# 5V_REG.net
KiCad netlist of a schematic drawn in Altium Designer
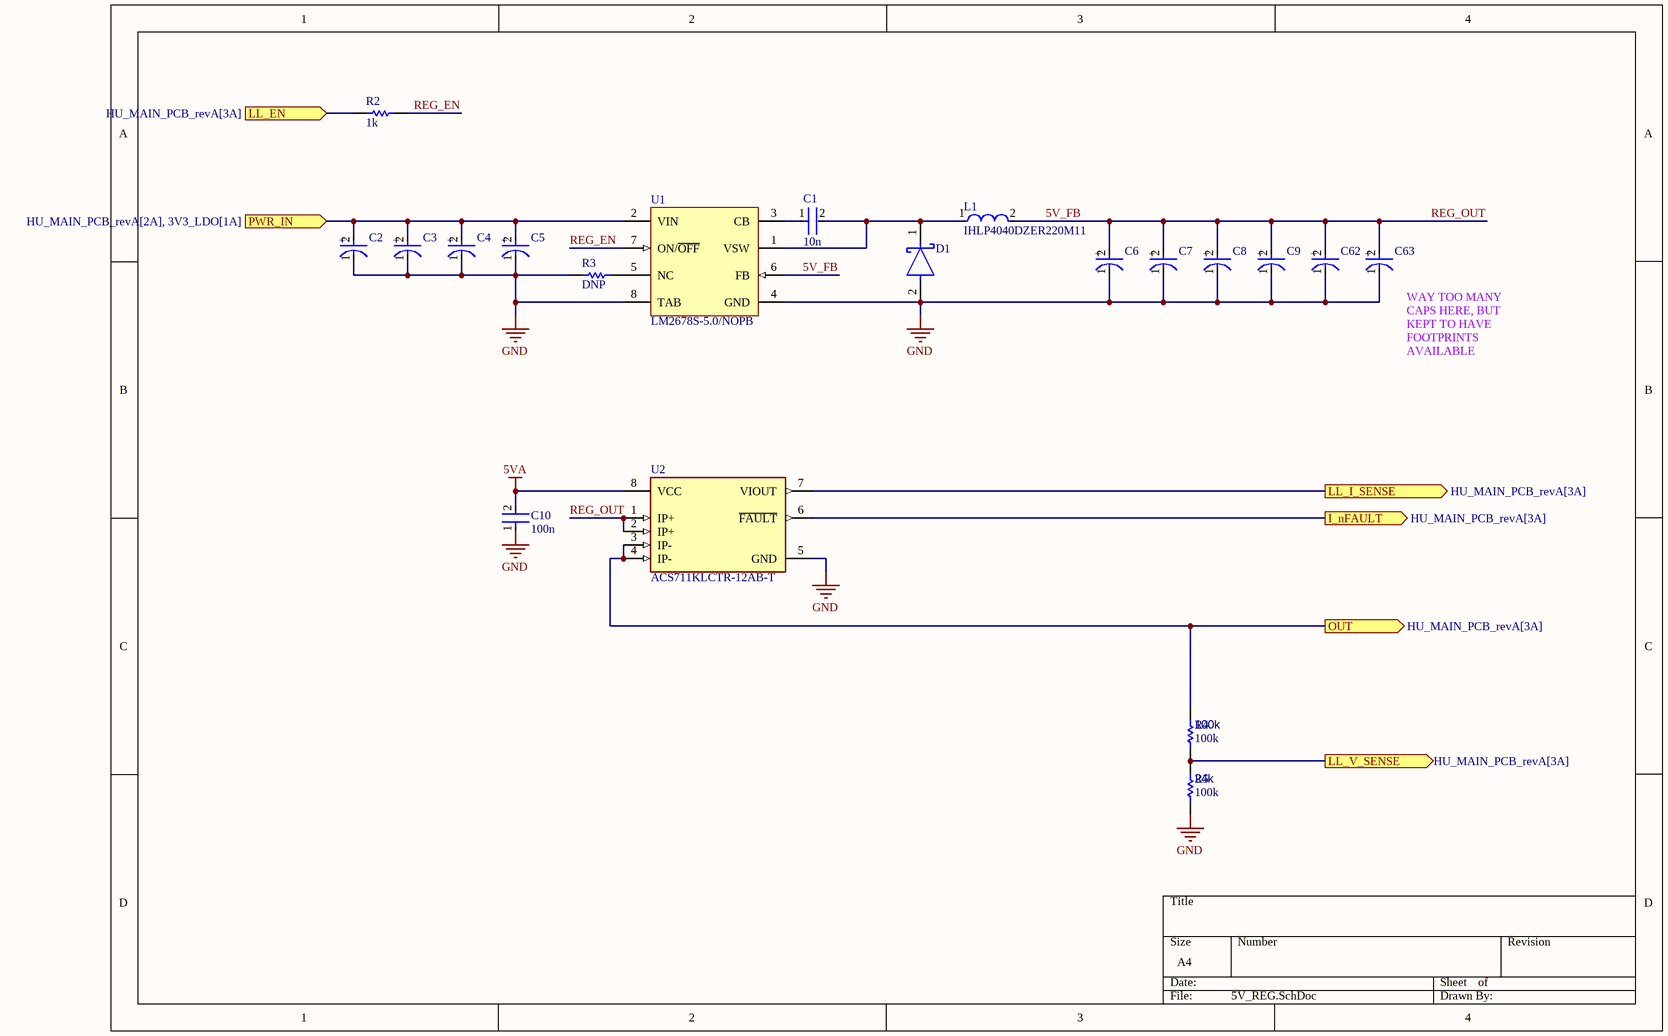
[diagram p0: 5V_REG.SchDoc]

(export (version "E")
  (design (tool "Eeschema 10.0.6"))
  (components
    (comp (ref "C1")
      (value "10n")
      (footprint "FP-0402-L_1_0_0_05-W_0_5-IPC_A")
      (description "LARGE PADS, 0402 CAP, CHANGE COMMENT TO MATCH REAL P/N")
      (libsource (lib "Space Concordia") (part "b4654b650e69147ec39a6b967a45e02"))
    )
    (comp (ref "C2")
      (value "TPSE686K025R0125")
      (footprint "FP-TPSE-MFG")
      (description "CAP TANT 68UF 10% 25V 2917")
      (fields (field (name "VOLTAGE") "25V") (field (name "TOLERANCE") "10%"))
      (libsource (lib "Altium Content Vault") (part "203bc49f2ac43e59fd269a8c329ed05"))
    )
    (comp (ref "C3")
      (value "TPSE686K025R0125")
      (footprint "FP-TPSE-MFG")
      (description "CAP TANT 68UF 10% 25V 2917")
      (fields (field (name "VOLTAGE") "25V") (field (name "TOLERANCE") "10%"))
      (libsource (lib "Altium Content Vault") (part "203bc49f2ac43e59fd269a8c329ed05"))
    )
    (comp (ref "C4")
      (value "TPSE686K025R0125")
      (footprint "FP-TPSE-MFG")
      (description "CAP TANT 68UF 10% 25V 2917")
      (fields (field (name "VOLTAGE") "25V") (field (name "TOLERANCE") "10%"))
      (libsource (lib "Altium Content Vault") (part "203bc49f2ac43e59fd269a8c329ed05"))
    )
    (comp (ref "C5")
      (value "TPSE686K025R0125")
      (footprint "FP-TPSE-MFG")
      (description "CAP TANT 68UF 10% 25V 2917")
      (fields (field (name "VOLTAGE") "25V") (field (name "TOLERANCE") "10%"))
      (libsource (lib "Altium Content Vault") (part "203bc49f2ac43e59fd269a8c329ed05"))
    )
    (comp (ref "C6")
      (value "TPSE686K025R0125")
      (footprint "FP-TPSE-MFG")
      (description "CAP TANT 68UF 10% 25V 2917")
      (fields (field (name "VOLTAGE") "25V") (field (name "TOLERANCE") "10%"))
      (libsource (lib "Altium Content Vault") (part "203bc49f2ac43e59fd269a8c329ed05"))
    )
    (comp (ref "C7")
      (value "TPSE686K025R0125")
      (footprint "FP-TPSE-MFG")
      (description "CAP TANT 68UF 10% 25V 2917")
      (fields (field (name "VOLTAGE") "25V") (field (name "TOLERANCE") "10%"))
      (libsource (lib "Altium Content Vault") (part "203bc49f2ac43e59fd269a8c329ed05"))
    )
    (comp (ref "C8")
      (value "TPSE686K025R0125")
      (footprint "FP-TPSE-MFG")
      (description "CAP TANT 68UF 10% 25V 2917")
      (fields (field (name "VOLTAGE") "25V") (field (name "TOLERANCE") "10%"))
      (libsource (lib "Altium Content Vault") (part "203bc49f2ac43e59fd269a8c329ed05"))
    )
    (comp (ref "C9")
      (value "TPSE686K025R0125")
      (footprint "FP-TPSE-MFG")
      (description "CAP TANT 68UF 10% 25V 2917")
      (fields (field (name "VOLTAGE") "25V") (field (name "TOLERANCE") "10%"))
      (libsource (lib "Altium Content Vault") (part "203bc49f2ac43e59fd269a8c329ed05"))
    )
    (comp (ref "C10")
      (value "100n")
      (footprint "FP-0402-L_1_0_0_05-W_0_5-IPC_A")
      (description "LARGE PADS, 0402 CAP, CHANGE COMMENT TO MATCH REAL P/N")
      (libsource (lib "Space Concordia") (part "b4654b650e69147ec39a6b967a45e02"))
    )
    (comp (ref "C62")
      (value "TPSE686K025R0125")
      (footprint "FP-TPSE-MFG")
      (description "CAP TANT 68UF 10% 25V 2917")
      (fields (field (name "VOLTAGE") "25V") (field (name "TOLERANCE") "10%"))
      (libsource (lib "Altium Content Vault") (part "203bc49f2ac43e59fd269a8c329ed05"))
    )
    (comp (ref "C63")
      (value "TPSE686K025R0125")
      (footprint "FP-TPSE-MFG")
      (description "CAP TANT 68UF 10% 25V 2917")
      (fields (field (name "VOLTAGE") "25V") (field (name "TOLERANCE") "10%"))
      (libsource (lib "Altium Content Vault") (part "203bc49f2ac43e59fd269a8c329ed05"))
    )
    (comp (ref "D1")
      (value "B540C-13-F")
      (footprint "FP-SMC-MFG")
      (description "DIODE SCHOTTKY 40V 5A SMC")
      (fields
        (field (name "OCTOPART") "https://octopart.com/b540c-13-f-diodes+inc.-325873")
        (field (name "MANUFACTURER") "Diodes Inc.")
      )
      (libsource (lib "Altium Content Vault") (part "1d6ec82d83fb6aee721767c19dac4b9"))
    )
    (comp (ref "L1")
      (value "IHLP4040DZER220M11")
      (footprint "FP-IHLP-4040DZ-FP_3_124x3-MFG")
      (description "Commercial Inductors, Low DCR Series 22uH 5A 66mΩ 20%")
      (fields (field (name "TOLERANCE") "20%"))
      (libsource (lib "Altium Content Vault") (part "725321dda6339637d4d059423bc1c3c"))
    )
    (comp (ref "R2")
      (value "1k")
      (footprint "R0603B")
      (description "Resistor")
      (libsource (lib "Space Concordia") (part "Resistor"))
    )
    (comp (ref "R3")
      (value "DNP")
      (footprint "R0603B")
      (description "Resistor")
      (libsource (lib "Space Concordia") (part "Resistor"))
    )
    (comp (ref "R4")
      (value "100k")
      (footprint "R0603B")
      (description "Resistor")
      (fields (field (name "ALTIUM_VALUE") "100k"))
      (libsource (lib "Space Concordia") (part "Resistor"))
    )
    (comp (ref "R5")
      (value "100k")
      (footprint "R0603B")
      (description "Resistor")
      (fields (field (name "ALTIUM_VALUE") "24k"))
      (libsource (lib "Space Concordia") (part "Resistor"))
    )
    (comp (ref "U1")
      (value "LM2678S-5.0/NOPB")
      (footprint "KTW0007B_L")
      (description "SIMPLE SWITCHER® High Efficiency 5A Step-Down Voltage Regulator, 7-pin TO-263, Pb-Free")
      (fields (field (name "MANUFACTURER") "Texas Instruments"))
      (libsource (lib "Altium Content Vault") (part "PM-REG-LM2678S"))
    )
    (comp (ref "U2")
      (value "ACS711KLCTR-12AB-T")
      (footprint "FP-LC-8-IPC_C")
      (description "SENSOR CURRENT HALL 12.5A AC/DC")
      (libsource (lib "Altium Content Vault") (part "b5e82308d4912bad35d89a98a7a92f9"))
    )
  )
  (nets
    (net (code "1") (name "/5V_FB") (class "Default")
      (node (ref "C6") (pin "2") (pinfunction "A_2") (pintype "passive"))
      (node (ref "C62") (pin "2") (pinfunction "A_2") (pintype "passive"))
      (node (ref "C63") (pin "2") (pinfunction "A_2") (pintype "passive"))
      (node (ref "C7") (pin "2") (pinfunction "A_2") (pintype "passive"))
      (node (ref "C8") (pin "2") (pinfunction "A_2") (pintype "passive"))
      (node (ref "C9") (pin "2") (pinfunction "A_2") (pintype "passive"))
      (node (ref "L1") (pin "2") (pinfunction "2_2") (pintype "passive"))
      (node (ref "U1") (pin "6") (pinfunction "FB_6") (pintype "input"))
      (node (ref "U2") (pin "1") (pinfunction "IP+_1") (pintype "input"))
      (node (ref "U2") (pin "2") (pinfunction "IP+_2") (pintype "input"))
    )
    (net (code "2") (name "/I_nFAULT") (class "Default")
      (node (ref "U2") (pin "6") (pinfunction "~{FAULT}_6") (pintype "output"))
    )
    (net (code "3") (name "/LL_EN") (class "Default")
      (node (ref "R2") (pin "2") (pinfunction "2_2") (pintype "passive"))
    )
    (net (code "4") (name "/LL_I_SENSE") (class "Default")
      (node (ref "U2") (pin "7") (pinfunction "VIOUT_7") (pintype "output"))
    )
    (net (code "5") (name "/LL_V_SENSE") (class "Default")
      (node (ref "R4") (pin "1") (pinfunction "1_1") (pintype "passive"))
      (node (ref "R5") (pin "2") (pinfunction "2_2") (pintype "passive"))
    )
    (net (code "6") (name "/OUT") (class "Default")
      (node (ref "R4") (pin "2") (pinfunction "2_2") (pintype "passive"))
      (node (ref "U2") (pin "3") (pinfunction "IP-_3") (pintype "input"))
      (node (ref "U2") (pin "4") (pinfunction "IP-_4") (pintype "input"))
    )
    (net (code "7") (name "/PWR_IN") (class "Default")
      (node (ref "C2") (pin "2") (pinfunction "A_2") (pintype "passive"))
      (node (ref "C3") (pin "2") (pinfunction "A_2") (pintype "passive"))
      (node (ref "C4") (pin "2") (pinfunction "A_2") (pintype "passive"))
      (node (ref "C5") (pin "2") (pinfunction "A_2") (pintype "passive"))
      (node (ref "U1") (pin "2") (pinfunction "VIN_2") (pintype "power_in"))
    )
    (net (code "8") (name "/REG_EN") (class "Default")
      (node (ref "R2") (pin "1") (pinfunction "1_1") (pintype "passive"))
      (node (ref "U1") (pin "7") (pinfunction "ON/~{OFF}_7") (pintype "input"))
    )
    (net (code "9") (name "5VA") (class "Default")
      (node (ref "C10") (pin "2") (pinfunction "2_2") (pintype "passive"))
      (node (ref "U2") (pin "8") (pinfunction "VCC_8") (pintype "power_in"))
    )
    (net (code "10") (name "GND") (class "Default")
      (node (ref "C10") (pin "1") (pinfunction "1_1") (pintype "passive"))
      (node (ref "C2") (pin "1") (pinfunction "C_1") (pintype "passive"))
      (node (ref "C3") (pin "1") (pinfunction "C_1") (pintype "passive"))
      (node (ref "C4") (pin "1") (pinfunction "C_1") (pintype "passive"))
      (node (ref "C5") (pin "1") (pinfunction "C_1") (pintype "passive"))
      (node (ref "C6") (pin "1") (pinfunction "C_1") (pintype "passive"))
      (node (ref "C62") (pin "1") (pinfunction "C_1") (pintype "passive"))
      (node (ref "C63") (pin "1") (pinfunction "C_1") (pintype "passive"))
      (node (ref "C7") (pin "1") (pinfunction "C_1") (pintype "passive"))
      (node (ref "C8") (pin "1") (pinfunction "C_1") (pintype "passive"))
      (node (ref "C9") (pin "1") (pinfunction "C_1") (pintype "passive"))
      (node (ref "D1") (pin "2") (pinfunction "A_2") (pintype "passive"))
      (node (ref "R3") (pin "2") (pinfunction "2_2") (pintype "passive"))
      (node (ref "R5") (pin "1") (pinfunction "1_1") (pintype "passive"))
      (node (ref "U1") (pin "4") (pinfunction "GND_4") (pintype "power_in"))
      (node (ref "U1") (pin "8") (pinfunction "TAB_8") (pintype "power_in"))
      (node (ref "U2") (pin "5") (pinfunction "GND_5") (pintype "power_in"))
    )
    (net (code "11") (name "Net-(D1-C)") (class "Default")
      (node (ref "C1") (pin "2") (pinfunction "2_2") (pintype "passive"))
      (node (ref "D1") (pin "1") (pinfunction "C_1") (pintype "passive"))
      (node (ref "L1") (pin "1") (pinfunction "1_1") (pintype "passive"))
      (node (ref "U1") (pin "1") (pinfunction "VSW_1") (pintype "power_in"))
    )
    (net (code "12") (name "Net-(U1-CB)") (class "Default")
      (node (ref "C1") (pin "1") (pinfunction "1_1") (pintype "passive"))
      (node (ref "U1") (pin "3") (pinfunction "CB_3") (pintype "passive"))
    )
    (net (code "13") (name "Net-(U1-NC)") (class "Default")
      (node (ref "R3") (pin "1") (pinfunction "1_1") (pintype "passive"))
      (node (ref "U1") (pin "5") (pinfunction "NC_5") (pintype "passive"))
    )
  )
)
